# openSX70-bench-new.net
KiCad netlist of a schematic drawn in EAGLE
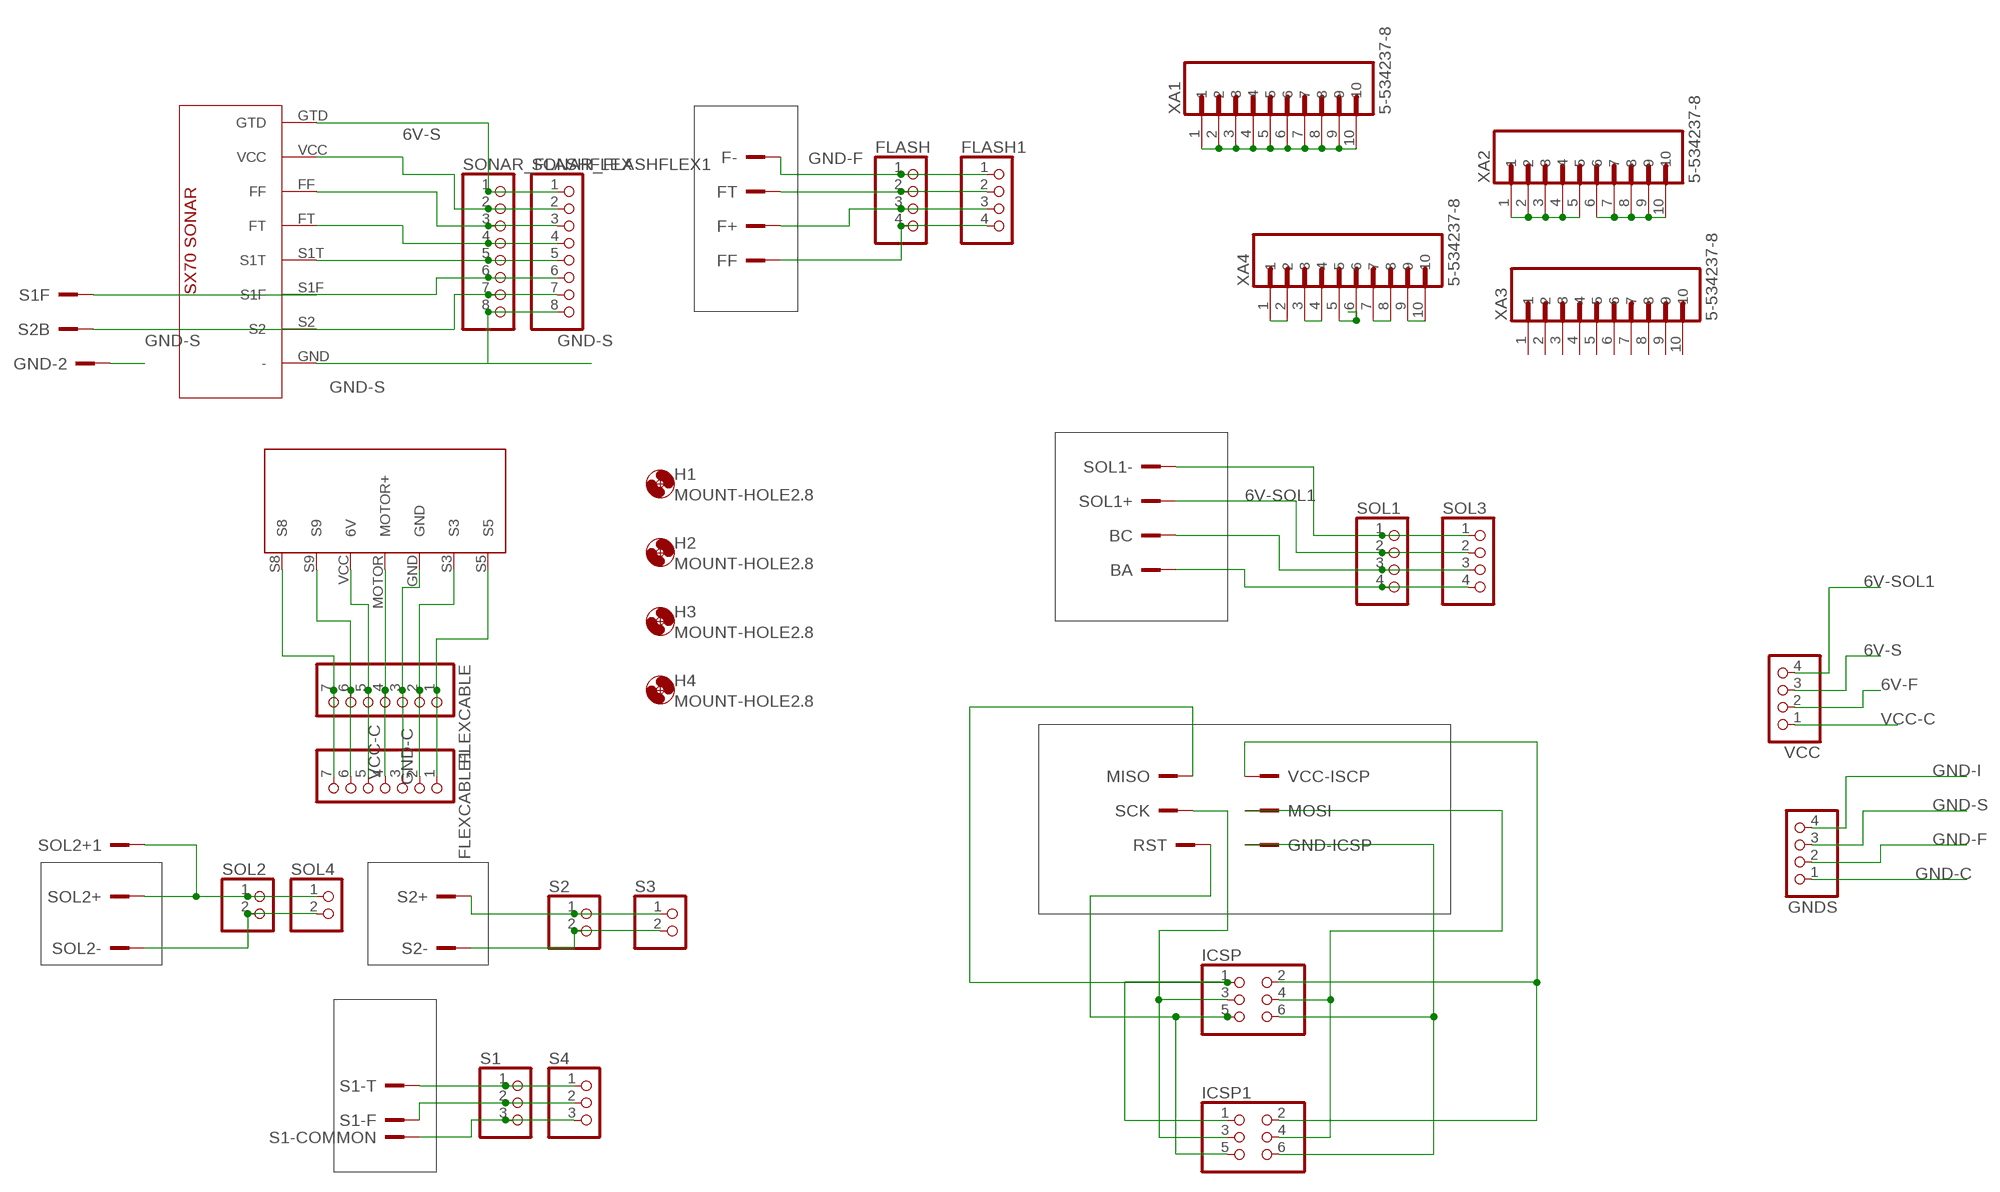
[diagram p0: schematic, sheet 1]

(export (version "E")
  (design (tool "Eeschema 10.0.6"))
  (components
    (comp (ref "BA")
      (value "PINHEAD")
      (footprint "eagle-import:1X01")
      (libsource (lib "eagle-import") (part "PINHEAD"))
    )
    (comp (ref "BC")
      (value "PINHEAD")
      (footprint "eagle-import:1X01")
      (libsource (lib "eagle-import") (part "PINHEAD"))
    )
    (comp (ref "F+")
      (value "PINHEAD")
      (footprint "eagle-import:1X01")
      (libsource (lib "eagle-import") (part "PINHEAD"))
    )
    (comp (ref "F-")
      (value "PINHEAD")
      (footprint "eagle-import:1X01")
      (libsource (lib "eagle-import") (part "PINHEAD"))
    )
    (comp (ref "FF")
      (value "PINHEAD")
      (footprint "eagle-import:1X01")
      (libsource (lib "eagle-import") (part "PINHEAD"))
    )
    (comp (ref "FLASH")
      (value "PINHD-1X4")
      (footprint "eagle-import:1X04")
      (libsource (lib "eagle-import") (part "PINHD-1X4"))
    )
    (comp (ref "FLASH1")
      (value "PINHD-1X4")
      (footprint "eagle-import:1X04")
      (libsource (lib "eagle-import") (part "PINHD-1X4"))
    )
    (comp (ref "FLEXCABLE")
      (value "PINHD-1X7")
      (footprint "eagle-import:1X07")
      (libsource (lib "eagle-import") (part "PINHD-1X7"))
    )
    (comp (ref "FLEXCABLE1")
      (value "PINHD-1X7")
      (footprint "eagle-import:1X07")
      (libsource (lib "eagle-import") (part "PINHD-1X7"))
    )
    (comp (ref "FT")
      (value "PINHEAD")
      (footprint "eagle-import:1X01")
      (libsource (lib "eagle-import") (part "PINHEAD"))
    )
    (comp (ref "GND-2")
      (value "PINHEAD")
      (footprint "eagle-import:1X01")
      (libsource (lib "eagle-import") (part "PINHEAD"))
    )
    (comp (ref "GND-ICSP")
      (value "PINHEAD")
      (footprint "eagle-import:1X01")
      (libsource (lib "eagle-import") (part "PINHEAD"))
    )
    (comp (ref "GNDS")
      (value "PINHD-1X4")
      (footprint "eagle-import:1X04")
      (libsource (lib "eagle-import") (part "PINHD-1X4"))
    )
    (comp (ref "H1")
      (value "MOUNT-HOLE2.8")
      (footprint "eagle-import:2,8")
      (libsource (lib "eagle-import") (part "MOUNT-HOLE2.8"))
    )
    (comp (ref "H2")
      (value "MOUNT-HOLE2.8")
      (footprint "eagle-import:2,8")
      (libsource (lib "eagle-import") (part "MOUNT-HOLE2.8"))
    )
    (comp (ref "H3")
      (value "MOUNT-HOLE2.8")
      (footprint "eagle-import:2,8")
      (libsource (lib "eagle-import") (part "MOUNT-HOLE2.8"))
    )
    (comp (ref "H4")
      (value "MOUNT-HOLE2.8")
      (footprint "eagle-import:2,8")
      (libsource (lib "eagle-import") (part "MOUNT-HOLE2.8"))
    )
    (comp (ref "ICSP")
      (value "PINHD-2X3")
      (footprint "eagle-import:2X03")
      (libsource (lib "eagle-import") (part "PINHD-2X3"))
    )
    (comp (ref "ICSP1")
      (value "PINHD-2X3")
      (footprint "eagle-import:2X03")
      (libsource (lib "eagle-import") (part "PINHD-2X3"))
    )
    (comp (ref "MISO")
      (value "PINHEAD")
      (footprint "eagle-import:1X01")
      (libsource (lib "eagle-import") (part "PINHEAD"))
    )
    (comp (ref "MOSI")
      (value "PINHEAD")
      (footprint "eagle-import:1X01")
      (libsource (lib "eagle-import") (part "PINHEAD"))
    )
    (comp (ref "RST")
      (value "PINHEAD")
      (footprint "eagle-import:1X01")
      (libsource (lib "eagle-import") (part "PINHEAD"))
    )
    (comp (ref "S1")
      (value "PINHD-1X3")
      (footprint "eagle-import:1X03")
      (libsource (lib "eagle-import") (part "PINHD-1X3"))
    )
    (comp (ref "S1-COMMON")
      (value "PINHEAD")
      (footprint "eagle-import:1X01")
      (libsource (lib "eagle-import") (part "PINHEAD"))
    )
    (comp (ref "S1-F")
      (value "PINHEAD")
      (footprint "eagle-import:1X01")
      (libsource (lib "eagle-import") (part "PINHEAD"))
    )
    (comp (ref "S1-T")
      (value "PINHEAD")
      (footprint "eagle-import:1X01")
      (libsource (lib "eagle-import") (part "PINHEAD"))
    )
    (comp (ref "S1F")
      (value "PINHEAD")
      (footprint "eagle-import:1X01")
      (libsource (lib "eagle-import") (part "PINHEAD"))
    )
    (comp (ref "S2")
      (value "PINHD-1X2")
      (footprint "eagle-import:1X02")
      (libsource (lib "eagle-import") (part "PINHD-1X2"))
    )
    (comp (ref "S2+")
      (value "PINHEAD")
      (footprint "eagle-import:1X01")
      (libsource (lib "eagle-import") (part "PINHEAD"))
    )
    (comp (ref "S2-")
      (value "PINHEAD")
      (footprint "eagle-import:1X01")
      (libsource (lib "eagle-import") (part "PINHEAD"))
    )
    (comp (ref "S2B")
      (value "PINHEAD")
      (footprint "eagle-import:1X01")
      (libsource (lib "eagle-import") (part "PINHEAD"))
    )
    (comp (ref "S3")
      (value "PINHD-1X2")
      (footprint "eagle-import:1X02")
      (libsource (lib "eagle-import") (part "PINHD-1X2"))
    )
    (comp (ref "S4")
      (value "PINHD-1X3")
      (footprint "eagle-import:1X03")
      (libsource (lib "eagle-import") (part "PINHD-1X3"))
    )
    (comp (ref "SCK")
      (value "PINHEAD")
      (footprint "eagle-import:1X01")
      (libsource (lib "eagle-import") (part "PINHEAD"))
    )
    (comp (ref "SOL1")
      (value "PINHD-1X4")
      (footprint "eagle-import:1X04")
      (libsource (lib "eagle-import") (part "PINHD-1X4"))
    )
    (comp (ref "SOL1+")
      (value "PINHEAD")
      (footprint "eagle-import:1X01")
      (libsource (lib "eagle-import") (part "PINHEAD"))
    )
    (comp (ref "SOL1-")
      (value "PINHEAD")
      (footprint "eagle-import:1X01")
      (libsource (lib "eagle-import") (part "PINHEAD"))
    )
    (comp (ref "SOL2")
      (value "PINHD-1X2")
      (footprint "eagle-import:1X02")
      (libsource (lib "eagle-import") (part "PINHD-1X2"))
    )
    (comp (ref "SOL2+")
      (value "PINHEAD")
      (footprint "eagle-import:1X01")
      (libsource (lib "eagle-import") (part "PINHEAD"))
    )
    (comp (ref "SOL2+1")
      (value "PINHEAD")
      (footprint "eagle-import:1X01")
      (libsource (lib "eagle-import") (part "PINHEAD"))
    )
    (comp (ref "SOL2-")
      (value "PINHEAD")
      (footprint "eagle-import:1X01")
      (libsource (lib "eagle-import") (part "PINHEAD"))
    )
    (comp (ref "SOL3")
      (value "PINHD-1X4")
      (footprint "eagle-import:1X04")
      (libsource (lib "eagle-import") (part "PINHD-1X4"))
    )
    (comp (ref "SOL4")
      (value "PINHD-1X2")
      (footprint "eagle-import:1X02")
      (libsource (lib "eagle-import") (part "PINHD-1X2"))
    )
    (comp (ref "SONAR_FLASHFLEX")
      (value "PINHD-1X8")
      (footprint "eagle-import:1X08")
      (libsource (lib "eagle-import") (part "PINHD-1X8"))
    )
    (comp (ref "SONAR_FLASHFLEX1")
      (value "PINHD-1X8")
      (footprint "eagle-import:1X08")
      (libsource (lib "eagle-import") (part "PINHD-1X8"))
    )
    (comp (ref "U$1")
      (value "SX70-7-PAD-HOLES-PROPER")
      (footprint "eagle-import:SX70-7-PAD-PROPER-HOLES2")
      (libsource (lib "eagle-import") (part "SX70-7-PAD-HOLES-PROPER"))
    )
    (comp (ref "U$2")
      (value "SX70-SONAR-FLASHFLEX-HOLES")
      (footprint "eagle-import:SONAR-FLASHFLEX-HOLES")
      (libsource (lib "eagle-import") (part "SX70-SONAR-FLASHFLEX-HOLES"))
    )
    (comp (ref "VCC")
      (value "PINHD-1X4")
      (footprint "eagle-import:1X04")
      (libsource (lib "eagle-import") (part "PINHD-1X4"))
    )
    (comp (ref "VCC-ISCP")
      (value "PINHEAD")
      (footprint "eagle-import:1X01")
      (libsource (lib "eagle-import") (part "PINHEAD"))
    )
    (comp (ref "XA1")
      (value "5-534237-8")
      (footprint "eagle-import:TE_5-534237-8")
      (fields (field (name "MANUFACTURER") "TE Connectivity"))
      (libsource (lib "eagle-import") (part "5-534237-8"))
    )
    (comp (ref "XA2")
      (value "5-534237-8")
      (footprint "eagle-import:TE_5-534237-8")
      (fields (field (name "MANUFACTURER") "TE Connectivity"))
      (libsource (lib "eagle-import") (part "5-534237-8"))
    )
    (comp (ref "XA3")
      (value "5-534237-8")
      (footprint "eagle-import:TE_5-534237-8")
      (fields (field (name "MANUFACTURER") "TE Connectivity"))
      (libsource (lib "eagle-import") (part "5-534237-8"))
    )
    (comp (ref "XA4")
      (value "5-534237-8")
      (footprint "eagle-import:TE_5-534237-8")
      (fields (field (name "MANUFACTURER") "TE Connectivity"))
      (libsource (lib "eagle-import") (part "5-534237-8"))
    )
  )
  (nets
    (net (code "1") (name "/6V-F") (class "Default")
      (node (ref "F+") (pin "1") (pinfunction "KL_1") (pintype "passive"))
      (node (ref "FLASH") (pin "3") (pinfunction "3_3") (pintype "passive"))
      (node (ref "FLASH1") (pin "3") (pinfunction "3_3") (pintype "passive"))
      (node (ref "VCC") (pin "2") (pinfunction "2_2") (pintype "passive"))
    )
    (net (code "2") (name "/6V-S") (class "Default")
      (node (ref "SONAR_FLASHFLEX") (pin "2") (pinfunction "2_2") (pintype "passive"))
      (node (ref "SONAR_FLASHFLEX1") (pin "2") (pinfunction "2_2") (pintype "passive"))
      (node (ref "U$2") (pin "VCC") (pinfunction "VCC_VCC") (pintype "bidirectional"))
      (node (ref "VCC") (pin "3") (pinfunction "3_3") (pintype "passive"))
    )
    (net (code "3") (name "/6V-SOL1") (class "Default")
      (node (ref "SOL1") (pin "2") (pinfunction "2_2") (pintype "passive"))
      (node (ref "SOL1+") (pin "1") (pinfunction "KL_1") (pintype "passive"))
      (node (ref "SOL3") (pin "2") (pinfunction "2_2") (pintype "passive"))
      (node (ref "VCC") (pin "4") (pinfunction "4_4") (pintype "passive"))
    )
    (net (code "4") (name "/GND-C") (class "Default")
      (node (ref "FLEXCABLE") (pin "3") (pinfunction "3_3") (pintype "passive"))
      (node (ref "FLEXCABLE1") (pin "3") (pinfunction "3_3") (pintype "passive"))
      (node (ref "GNDS") (pin "1") (pinfunction "1_1") (pintype "passive"))
      (node (ref "U$1") (pin "GND") (pinfunction "GND_GND") (pintype "bidirectional"))
    )
    (net (code "5") (name "/GND-F") (class "Default")
      (node (ref "F-") (pin "1") (pinfunction "KL_1") (pintype "passive"))
      (node (ref "FLASH") (pin "1") (pinfunction "1_1") (pintype "passive"))
      (node (ref "FLASH1") (pin "1") (pinfunction "1_1") (pintype "passive"))
      (node (ref "GNDS") (pin "2") (pinfunction "2_2") (pintype "passive"))
    )
    (net (code "6") (name "/GND-I") (class "Default")
      (node (ref "GND-ICSP") (pin "1") (pinfunction "KL_1") (pintype "passive"))
      (node (ref "GNDS") (pin "4") (pinfunction "4_4") (pintype "passive"))
      (node (ref "ICSP") (pin "6") (pinfunction "6_6") (pintype "passive"))
      (node (ref "ICSP1") (pin "6") (pinfunction "6_6") (pintype "passive"))
    )
    (net (code "7") (name "/GND-S") (class "Default")
      (node (ref "GND-2") (pin "1") (pinfunction "KL_1") (pintype "passive"))
      (node (ref "GNDS") (pin "3") (pinfunction "3_3") (pintype "passive"))
      (node (ref "SONAR_FLASHFLEX") (pin "8") (pinfunction "8_8") (pintype "passive"))
      (node (ref "SONAR_FLASHFLEX1") (pin "8") (pinfunction "8_8") (pintype "passive"))
      (node (ref "U$2") (pin "GND") (pinfunction "-_GND") (pintype "bidirectional"))
    )
    (net (code "8") (name "/VCC-C") (class "Default")
      (node (ref "FLEXCABLE") (pin "5") (pinfunction "5_5") (pintype "passive"))
      (node (ref "FLEXCABLE1") (pin "5") (pinfunction "5_5") (pintype "passive"))
      (node (ref "U$1") (pin "VCC") (pinfunction "6V_VCC") (pintype "bidirectional"))
      (node (ref "VCC") (pin "1") (pinfunction "1_1") (pintype "passive"))
    )
    (net (code "9") (name "Net-(BA-KL)") (class "Default")
      (node (ref "BA") (pin "1") (pinfunction "KL_1") (pintype "passive"))
      (node (ref "SOL1") (pin "4") (pinfunction "4_4") (pintype "passive"))
      (node (ref "SOL3") (pin "4") (pinfunction "4_4") (pintype "passive"))
    )
    (net (code "10") (name "Net-(BC-KL)") (class "Default")
      (node (ref "BC") (pin "1") (pinfunction "KL_1") (pintype "passive"))
      (node (ref "SOL1") (pin "3") (pinfunction "3_3") (pintype "passive"))
      (node (ref "SOL3") (pin "3") (pinfunction "3_3") (pintype "passive"))
    )
    (net (code "11") (name "Net-(FF-KL)") (class "Default")
      (node (ref "FF") (pin "1") (pinfunction "KL_1") (pintype "passive"))
      (node (ref "FLASH") (pin "4") (pinfunction "4_4") (pintype "passive"))
      (node (ref "FLASH1") (pin "4") (pinfunction "4_4") (pintype "passive"))
    )
    (net (code "12") (name "Net-(FLEXCABLE-Pad1)") (class "Default")
      (node (ref "FLEXCABLE") (pin "1") (pinfunction "1_1") (pintype "passive"))
      (node (ref "FLEXCABLE1") (pin "1") (pinfunction "1_1") (pintype "passive"))
      (node (ref "U$1") (pin "S5") (pinfunction "S5_S5") (pintype "bidirectional"))
    )
    (net (code "13") (name "Net-(FLEXCABLE-Pad2)") (class "Default")
      (node (ref "FLEXCABLE") (pin "2") (pinfunction "2_2") (pintype "passive"))
      (node (ref "FLEXCABLE1") (pin "2") (pinfunction "2_2") (pintype "passive"))
      (node (ref "U$1") (pin "S3") (pinfunction "S3_S3") (pintype "bidirectional"))
    )
    (net (code "14") (name "Net-(FLEXCABLE-Pad6)") (class "Default")
      (node (ref "FLEXCABLE") (pin "6") (pinfunction "6_6") (pintype "passive"))
      (node (ref "FLEXCABLE1") (pin "6") (pinfunction "6_6") (pintype "passive"))
      (node (ref "U$1") (pin "S9") (pinfunction "S9_S9") (pintype "bidirectional"))
    )
    (net (code "15") (name "Net-(FLEXCABLE-Pad7)") (class "Default")
      (node (ref "FLEXCABLE") (pin "7") (pinfunction "7_7") (pintype "passive"))
      (node (ref "FLEXCABLE1") (pin "7") (pinfunction "7_7") (pintype "passive"))
      (node (ref "U$1") (pin "S8") (pinfunction "S8_S8") (pintype "bidirectional"))
    )
    (net (code "16") (name "Net-(FT-KL)") (class "Default")
      (node (ref "FLASH") (pin "2") (pinfunction "2_2") (pintype "passive"))
      (node (ref "FLASH1") (pin "2") (pinfunction "2_2") (pintype "passive"))
      (node (ref "FT") (pin "1") (pinfunction "KL_1") (pintype "passive"))
    )
    (net (code "17") (name "Net-(MISO-KL)") (class "Default")
      (node (ref "ICSP") (pin "1") (pinfunction "1_1") (pintype "passive"))
      (node (ref "ICSP1") (pin "1") (pinfunction "1_1") (pintype "passive"))
      (node (ref "MISO") (pin "1") (pinfunction "KL_1") (pintype "passive"))
    )
    (net (code "18") (name "Net-(MOSI-KL)") (class "Default")
      (node (ref "ICSP") (pin "4") (pinfunction "4_4") (pintype "passive"))
      (node (ref "ICSP1") (pin "4") (pinfunction "4_4") (pintype "passive"))
      (node (ref "MOSI") (pin "1") (pinfunction "KL_1") (pintype "passive"))
    )
    (net (code "19") (name "Net-(RST-KL)") (class "Default")
      (node (ref "ICSP") (pin "5") (pinfunction "5_5") (pintype "passive"))
      (node (ref "ICSP1") (pin "5") (pinfunction "5_5") (pintype "passive"))
      (node (ref "RST") (pin "1") (pinfunction "KL_1") (pintype "passive"))
    )
    (net (code "20") (name "Net-(S1-COMMON-KL)") (class "Default")
      (node (ref "S1") (pin "3") (pinfunction "3_3") (pintype "passive"))
      (node (ref "S1-COMMON") (pin "1") (pinfunction "KL_1") (pintype "passive"))
      (node (ref "S4") (pin "3") (pinfunction "3_3") (pintype "passive"))
    )
    (net (code "21") (name "Net-(S1-F-KL)") (class "Default")
      (node (ref "S1") (pin "2") (pinfunction "2_2") (pintype "passive"))
      (node (ref "S1-F") (pin "1") (pinfunction "KL_1") (pintype "passive"))
      (node (ref "S4") (pin "2") (pinfunction "2_2") (pintype "passive"))
    )
    (net (code "22") (name "Net-(S1-T-KL)") (class "Default")
      (node (ref "S1") (pin "1") (pinfunction "1_1") (pintype "passive"))
      (node (ref "S1-T") (pin "1") (pinfunction "KL_1") (pintype "passive"))
      (node (ref "S4") (pin "1") (pinfunction "1_1") (pintype "passive"))
    )
    (net (code "23") (name "Net-(S1F-KL)") (class "Default")
      (node (ref "S1F") (pin "1") (pinfunction "KL_1") (pintype "passive"))
      (node (ref "SONAR_FLASHFLEX") (pin "6") (pinfunction "6_6") (pintype "passive"))
      (node (ref "SONAR_FLASHFLEX1") (pin "6") (pinfunction "6_6") (pintype "passive"))
      (node (ref "U$2") (pin "S1F") (pinfunction "S1F_S1F") (pintype "bidirectional"))
    )
    (net (code "24") (name "Net-(S2+-KL)") (class "Default")
      (node (ref "S2") (pin "1") (pinfunction "1_1") (pintype "passive"))
      (node (ref "S2+") (pin "1") (pinfunction "KL_1") (pintype "passive"))
      (node (ref "S3") (pin "1") (pinfunction "1_1") (pintype "passive"))
    )
    (net (code "25") (name "Net-(S2--KL)") (class "Default")
      (node (ref "S2") (pin "2") (pinfunction "2_2") (pintype "passive"))
      (node (ref "S2-") (pin "1") (pinfunction "KL_1") (pintype "passive"))
      (node (ref "S3") (pin "2") (pinfunction "2_2") (pintype "passive"))
    )
    (net (code "26") (name "Net-(S2B-KL)") (class "Default")
      (node (ref "S2B") (pin "1") (pinfunction "KL_1") (pintype "passive"))
      (node (ref "SONAR_FLASHFLEX") (pin "7") (pinfunction "7_7") (pintype "passive"))
      (node (ref "SONAR_FLASHFLEX1") (pin "7") (pinfunction "7_7") (pintype "passive"))
      (node (ref "U$2") (pin "S2") (pinfunction "S2_S2") (pintype "bidirectional"))
    )
    (net (code "27") (name "Net-(SCK-KL)") (class "Default")
      (node (ref "ICSP") (pin "3") (pinfunction "3_3") (pintype "passive"))
      (node (ref "ICSP1") (pin "3") (pinfunction "3_3") (pintype "passive"))
      (node (ref "SCK") (pin "1") (pinfunction "KL_1") (pintype "passive"))
    )
    (net (code "28") (name "Net-(SOL1--KL)") (class "Default")
      (node (ref "SOL1") (pin "1") (pinfunction "1_1") (pintype "passive"))
      (node (ref "SOL1-") (pin "1") (pinfunction "KL_1") (pintype "passive"))
      (node (ref "SOL3") (pin "1") (pinfunction "1_1") (pintype "passive"))
    )
    (net (code "29") (name "Net-(SOL2+-KL)") (class "Default")
      (node (ref "SOL2") (pin "1") (pinfunction "1_1") (pintype "passive"))
      (node (ref "SOL2+") (pin "1") (pinfunction "KL_1") (pintype "passive"))
      (node (ref "SOL2+1") (pin "1") (pinfunction "KL_1") (pintype "passive"))
      (node (ref "SOL4") (pin "1") (pinfunction "1_1") (pintype "passive"))
    )
    (net (code "30") (name "Net-(SOL2--KL)") (class "Default")
      (node (ref "SOL2") (pin "2") (pinfunction "2_2") (pintype "passive"))
      (node (ref "SOL2-") (pin "1") (pinfunction "KL_1") (pintype "passive"))
      (node (ref "SOL4") (pin "2") (pinfunction "2_2") (pintype "passive"))
    )
    (net (code "31") (name "Net-(SONAR_FLASHFLEX-Pad1)") (class "Default")
      (node (ref "SONAR_FLASHFLEX") (pin "1") (pinfunction "1_1") (pintype "passive"))
      (node (ref "SONAR_FLASHFLEX1") (pin "1") (pinfunction "1_1") (pintype "passive"))
      (node (ref "U$2") (pin "GTD") (pinfunction "GTD_GTD") (pintype "bidirectional"))
    )
    (net (code "32") (name "Net-(SONAR_FLASHFLEX-Pad3)") (class "Default")
      (node (ref "SONAR_FLASHFLEX") (pin "3") (pinfunction "3_3") (pintype "passive"))
      (node (ref "SONAR_FLASHFLEX1") (pin "3") (pinfunction "3_3") (pintype "passive"))
      (node (ref "U$2") (pin "FF") (pinfunction "FF_FF") (pintype "bidirectional"))
    )
    (net (code "33") (name "Net-(SONAR_FLASHFLEX-Pad4)") (class "Default")
      (node (ref "SONAR_FLASHFLEX") (pin "4") (pinfunction "4_4") (pintype "passive"))
      (node (ref "SONAR_FLASHFLEX1") (pin "4") (pinfunction "4_4") (pintype "passive"))
      (node (ref "U$2") (pin "FT") (pinfunction "FT_FT") (pintype "bidirectional"))
    )
    (net (code "34") (name "Net-(SONAR_FLASHFLEX-Pad5)") (class "Default")
      (node (ref "SONAR_FLASHFLEX") (pin "5") (pinfunction "5_5") (pintype "passive"))
      (node (ref "SONAR_FLASHFLEX1") (pin "5") (pinfunction "5_5") (pintype "passive"))
      (node (ref "U$2") (pin "S1T") (pinfunction "S1T_S1T") (pintype "bidirectional"))
    )
    (net (code "35") (name "Net-(U$1-MOTOR+)") (class "Default")
      (node (ref "FLEXCABLE") (pin "4") (pinfunction "4_4") (pintype "passive"))
      (node (ref "FLEXCABLE1") (pin "4") (pinfunction "4_4") (pintype "passive"))
      (node (ref "U$1") (pin "MOTOR") (pinfunction "MOTOR+_MOTOR") (pintype "bidirectional"))
    )
    (net (code "36") (name "Net-(VCC-ISCP-KL)") (class "Default")
      (node (ref "ICSP") (pin "2") (pinfunction "2_2") (pintype "passive"))
      (node (ref "ICSP1") (pin "2") (pinfunction "2_2") (pintype "passive"))
      (node (ref "VCC-ISCP") (pin "1") (pinfunction "KL_1") (pintype "passive"))
    )
    (net (code "37") (name "Net-(XA1-Pad1)") (class "Default")
      (node (ref "XA1") (pin "1") (pinfunction "1_1") (pintype "passive"))
      (node (ref "XA1") (pin "10") (pinfunction "10_10") (pintype "passive"))
      (node (ref "XA1") (pin "2") (pinfunction "2_2") (pintype "passive"))
      (node (ref "XA1") (pin "3") (pinfunction "3_3") (pintype "passive"))
      (node (ref "XA1") (pin "4") (pinfunction "4_4") (pintype "passive"))
      (node (ref "XA1") (pin "5") (pinfunction "5_5") (pintype "passive"))
      (node (ref "XA1") (pin "6") (pinfunction "6_6") (pintype "passive"))
      (node (ref "XA1") (pin "7") (pinfunction "7_7") (pintype "passive"))
      (node (ref "XA1") (pin "8") (pinfunction "8_8") (pintype "passive"))
      (node (ref "XA1") (pin "9") (pinfunction "9_9") (pintype "passive"))
    )
    (net (code "38") (name "Net-(XA2-Pad1)") (class "Default")
      (node (ref "XA2") (pin "1") (pinfunction "1_1") (pintype "passive"))
      (node (ref "XA2") (pin "2") (pinfunction "2_2") (pintype "passive"))
      (node (ref "XA2") (pin "3") (pinfunction "3_3") (pintype "passive"))
      (node (ref "XA2") (pin "4") (pinfunction "4_4") (pintype "passive"))
      (node (ref "XA2") (pin "5") (pinfunction "5_5") (pintype "passive"))
    )
    (net (code "39") (name "Net-(XA2-Pad10)") (class "Default")
      (node (ref "XA2") (pin "10") (pinfunction "10_10") (pintype "passive"))
      (node (ref "XA2") (pin "6") (pinfunction "6_6") (pintype "passive"))
      (node (ref "XA2") (pin "7") (pinfunction "7_7") (pintype "passive"))
      (node (ref "XA2") (pin "8") (pinfunction "8_8") (pintype "passive"))
      (node (ref "XA2") (pin "9") (pinfunction "9_9") (pintype "passive"))
    )
    (net (code "40") (name "Net-(XA4-Pad1)") (class "Default")
      (node (ref "XA4") (pin "1") (pinfunction "1_1") (pintype "passive"))
      (node (ref "XA4") (pin "2") (pinfunction "2_2") (pintype "passive"))
    )
    (net (code "41") (name "Net-(XA4-Pad3)") (class "Default")
      (node (ref "XA4") (pin "3") (pinfunction "3_3") (pintype "passive"))
      (node (ref "XA4") (pin "4") (pinfunction "4_4") (pintype "passive"))
    )
    (net (code "42") (name "Net-(XA4-Pad5)") (class "Default")
      (node (ref "XA4") (pin "5") (pinfunction "5_5") (pintype "passive"))
      (node (ref "XA4") (pin "6") (pinfunction "6_6") (pintype "passive"))
    )
    (net (code "43") (name "Net-(XA4-Pad7)") (class "Default")
      (node (ref "XA4") (pin "7") (pinfunction "7_7") (pintype "passive"))
      (node (ref "XA4") (pin "8") (pinfunction "8_8") (pintype "passive"))
    )
    (net (code "44") (name "Net-(XA4-Pad10)") (class "Default")
      (node (ref "XA4") (pin "10") (pinfunction "10_10") (pintype "passive"))
      (node (ref "XA4") (pin "9") (pinfunction "9_9") (pintype "passive"))
    )
    (net (code "45") (name "unconnected-(XA3-Pad1)") (class "Default")
      (node (ref "XA3") (pin "1") (pinfunction "1_1") (pintype "passive"))
    )
    (net (code "46") (name "unconnected-(XA3-Pad2)") (class "Default")
      (node (ref "XA3") (pin "2") (pinfunction "2_2") (pintype "passive"))
    )
    (net (code "47") (name "unconnected-(XA3-Pad3)") (class "Default")
      (node (ref "XA3") (pin "3") (pinfunction "3_3") (pintype "passive"))
    )
    (net (code "48") (name "unconnected-(XA3-Pad4)") (class "Default")
      (node (ref "XA3") (pin "4") (pinfunction "4_4") (pintype "passive"))
    )
    (net (code "49") (name "unconnected-(XA3-Pad5)") (class "Default")
      (node (ref "XA3") (pin "5") (pinfunction "5_5") (pintype "passive"))
    )
    (net (code "50") (name "unconnected-(XA3-Pad6)") (class "Default")
      (node (ref "XA3") (pin "6") (pinfunction "6_6") (pintype "passive"))
    )
    (net (code "51") (name "unconnected-(XA3-Pad7)") (class "Default")
      (node (ref "XA3") (pin "7") (pinfunction "7_7") (pintype "passive"))
    )
    (net (code "52") (name "unconnected-(XA3-Pad8)") (class "Default")
      (node (ref "XA3") (pin "8") (pinfunction "8_8") (pintype "passive"))
    )
    (net (code "53") (name "unconnected-(XA3-Pad9)") (class "Default")
      (node (ref "XA3") (pin "9") (pinfunction "9_9") (pintype "passive"))
    )
    (net (code "54") (name "unconnected-(XA3-Pad10)") (class "Default")
      (node (ref "XA3") (pin "10") (pinfunction "10_10") (pintype "passive"))
    )
  )
)
